# Hardware-Neuron.net
KiCad netlist of a schematic drawn in EAGLE
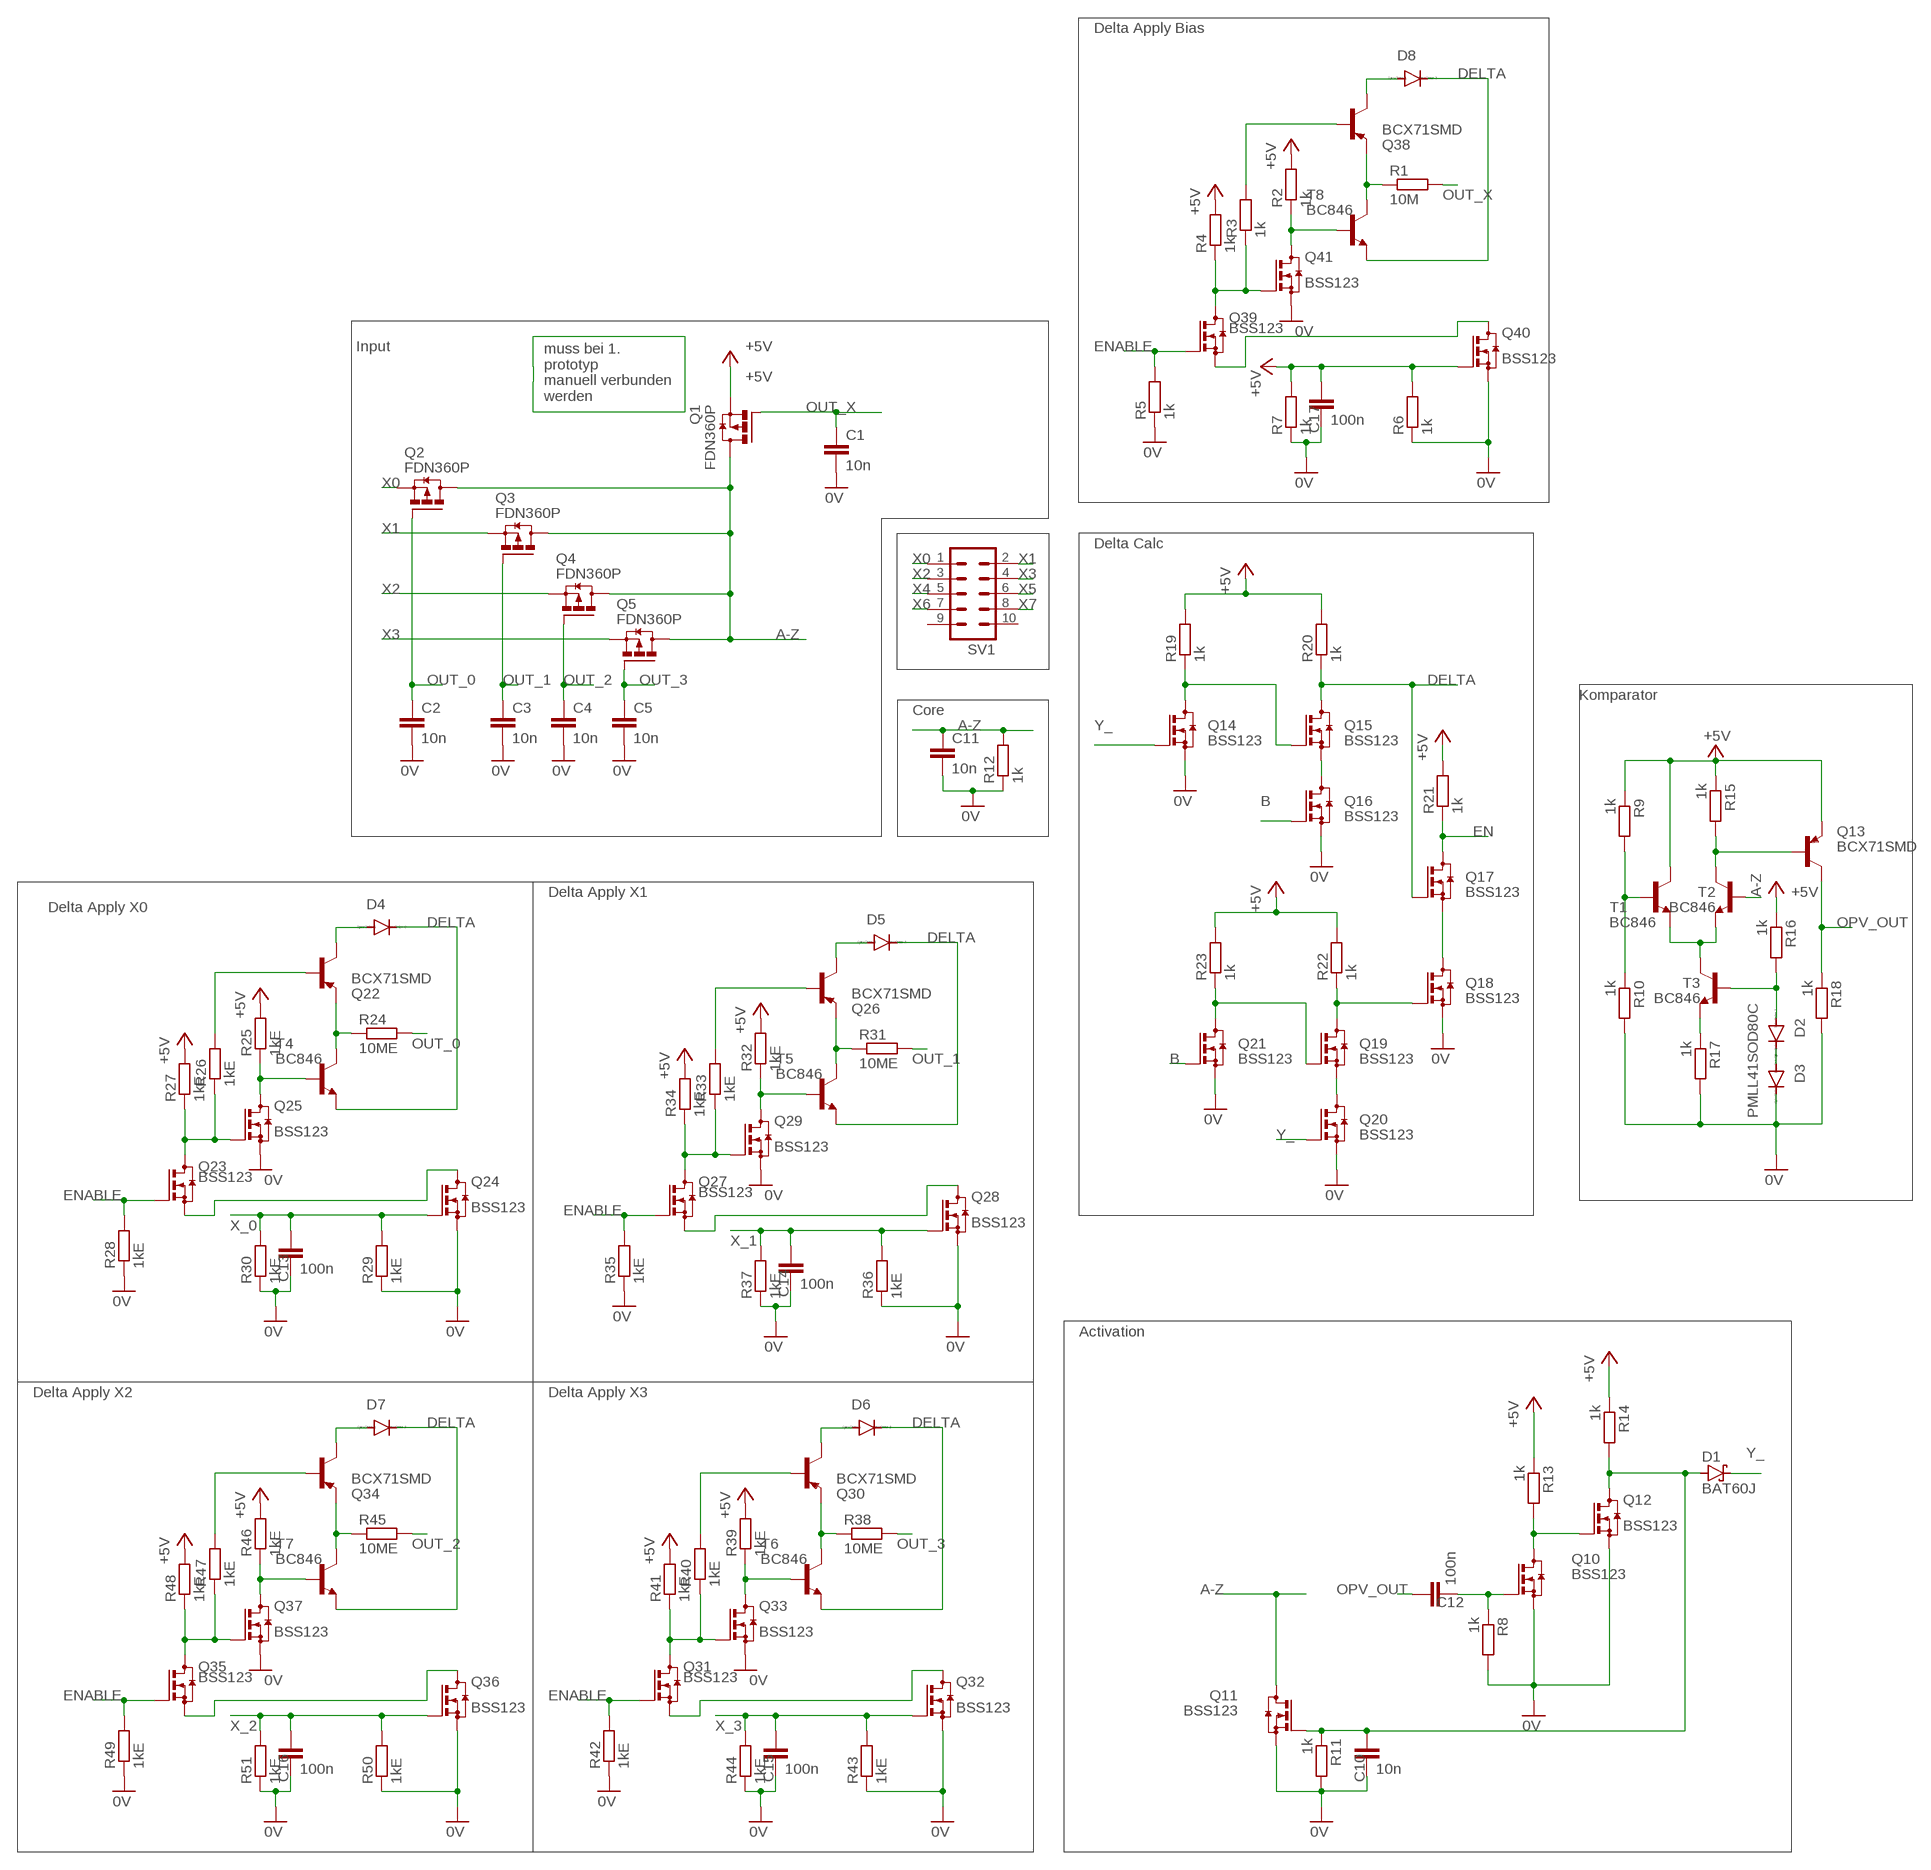
[diagram p0: schematic, sheet 1]

(export (version "E")
  (design (tool "Eeschema 10.0.6"))
  (components
    (comp (ref "C1")
      (value "10n")
      (footprint "eagle-import:C1206")
      (libsource (lib "eagle-import") (part "C-EUC1206"))
    )
    (comp (ref "C2")
      (value "10n")
      (footprint "eagle-import:C1206")
      (libsource (lib "eagle-import") (part "C-EUC1206"))
    )
    (comp (ref "C3")
      (value "10n")
      (footprint "eagle-import:C1206")
      (libsource (lib "eagle-import") (part "C-EUC1206"))
    )
    (comp (ref "C4")
      (value "10n")
      (footprint "eagle-import:C1206")
      (libsource (lib "eagle-import") (part "C-EUC1206"))
    )
    (comp (ref "C5")
      (value "10n")
      (footprint "eagle-import:C1206")
      (libsource (lib "eagle-import") (part "C-EUC1206"))
    )
    (comp (ref "C10")
      (value "10n")
      (footprint "eagle-import:C1206")
      (libsource (lib "eagle-import") (part "C-EUC1206"))
    )
    (comp (ref "C11")
      (value "10n")
      (footprint "eagle-import:C1206")
      (libsource (lib "eagle-import") (part "C-EUC1206"))
    )
    (comp (ref "C12")
      (value "100n")
      (footprint "eagle-import:C1206")
      (libsource (lib "eagle-import") (part "C-EUC1206"))
    )
    (comp (ref "C13")
      (value "100n")
      (footprint "eagle-import:C1206")
      (libsource (lib "eagle-import") (part "C-EUC1206"))
    )
    (comp (ref "C14")
      (value "100n")
      (footprint "eagle-import:C1206")
      (libsource (lib "eagle-import") (part "C-EUC1206"))
    )
    (comp (ref "C15")
      (value "100n")
      (footprint "eagle-import:C1206")
      (libsource (lib "eagle-import") (part "C-EUC1206"))
    )
    (comp (ref "C16")
      (value "100n")
      (footprint "eagle-import:C1206")
      (libsource (lib "eagle-import") (part "C-EUC1206"))
    )
    (comp (ref "C17")
      (value "100n")
      (footprint "eagle-import:C1206")
      (libsource (lib "eagle-import") (part "C-EUC1206"))
    )
    (comp (ref "D1")
      (value "BAT60J")
      (footprint "eagle-import:SOD323_ST")
      (libsource (lib "eagle-import") (part "BAT60J"))
    )
    (comp (ref "D2")
      (value "PMLL41SOD80C")
      (footprint "eagle-import:SOD80C")
      (libsource (lib "eagle-import") (part "PMLL41SOD80C"))
    )
    (comp (ref "D3")
      (value "PMLL41SOD80C")
      (footprint "eagle-import:SOD80C")
      (libsource (lib "eagle-import") (part "PMLL41SOD80C"))
    )
    (comp (ref "D4")
      (value "PMLL41SOD80C")
      (footprint "eagle-import:SOD80C")
      (libsource (lib "eagle-import") (part "PMLL41SOD80C"))
    )
    (comp (ref "D5")
      (value "PMLL41SOD80C")
      (footprint "eagle-import:SOD80C")
      (libsource (lib "eagle-import") (part "PMLL41SOD80C"))
    )
    (comp (ref "D6")
      (value "PMLL41SOD80C")
      (footprint "eagle-import:SOD80C")
      (libsource (lib "eagle-import") (part "PMLL41SOD80C"))
    )
    (comp (ref "D7")
      (value "PMLL41SOD80C")
      (footprint "eagle-import:SOD80C")
      (libsource (lib "eagle-import") (part "PMLL41SOD80C"))
    )
    (comp (ref "D8")
      (value "PMLL41SOD80C")
      (footprint "eagle-import:SOD80C")
      (libsource (lib "eagle-import") (part "PMLL41SOD80C"))
    )
    (comp (ref "Q1")
      (value "FDN360P")
      (footprint "eagle-import:SUPER-SOT3")
      (libsource (lib "eagle-import") (part "FDN360P"))
    )
    (comp (ref "Q2")
      (value "FDN360P")
      (footprint "eagle-import:SUPER-SOT3")
      (libsource (lib "eagle-import") (part "FDN360P"))
    )
    (comp (ref "Q3")
      (value "FDN360P")
      (footprint "eagle-import:SUPER-SOT3")
      (libsource (lib "eagle-import") (part "FDN360P"))
    )
    (comp (ref "Q4")
      (value "FDN360P")
      (footprint "eagle-import:SUPER-SOT3")
      (libsource (lib "eagle-import") (part "FDN360P"))
    )
    (comp (ref "Q5")
      (value "FDN360P")
      (footprint "eagle-import:SUPER-SOT3")
      (libsource (lib "eagle-import") (part "FDN360P"))
    )
    (comp (ref "Q10")
      (value "BSS123")
      (footprint "eagle-import:SOT23")
      (libsource (lib "eagle-import") (part "BSS123"))
    )
    (comp (ref "Q11")
      (value "BSS123")
      (footprint "eagle-import:SOT23")
      (libsource (lib "eagle-import") (part "BSS123"))
    )
    (comp (ref "Q12")
      (value "BSS123")
      (footprint "eagle-import:SOT23")
      (libsource (lib "eagle-import") (part "BSS123"))
    )
    (comp (ref "Q13")
      (value "BCX71SMD")
      (footprint "eagle-import:SOT23")
      (libsource (lib "eagle-import") (part "BCX71SMD"))
    )
    (comp (ref "Q14")
      (value "BSS123")
      (footprint "eagle-import:SOT23")
      (libsource (lib "eagle-import") (part "BSS123"))
    )
    (comp (ref "Q15")
      (value "BSS123")
      (footprint "eagle-import:SOT23")
      (libsource (lib "eagle-import") (part "BSS123"))
    )
    (comp (ref "Q16")
      (value "BSS123")
      (footprint "eagle-import:SOT23")
      (libsource (lib "eagle-import") (part "BSS123"))
    )
    (comp (ref "Q17")
      (value "BSS123")
      (footprint "eagle-import:SOT23")
      (libsource (lib "eagle-import") (part "BSS123"))
    )
    (comp (ref "Q18")
      (value "BSS123")
      (footprint "eagle-import:SOT23")
      (libsource (lib "eagle-import") (part "BSS123"))
    )
    (comp (ref "Q19")
      (value "BSS123")
      (footprint "eagle-import:SOT23")
      (libsource (lib "eagle-import") (part "BSS123"))
    )
    (comp (ref "Q20")
      (value "BSS123")
      (footprint "eagle-import:SOT23")
      (libsource (lib "eagle-import") (part "BSS123"))
    )
    (comp (ref "Q21")
      (value "BSS123")
      (footprint "eagle-import:SOT23")
      (libsource (lib "eagle-import") (part "BSS123"))
    )
    (comp (ref "Q22")
      (value "BCX71SMD")
      (footprint "eagle-import:SOT23")
      (libsource (lib "eagle-import") (part "BCX71SMD"))
    )
    (comp (ref "Q23")
      (value "BSS123")
      (footprint "eagle-import:SOT23")
      (libsource (lib "eagle-import") (part "BSS123"))
    )
    (comp (ref "Q24")
      (value "BSS123")
      (footprint "eagle-import:SOT23")
      (libsource (lib "eagle-import") (part "BSS123"))
    )
    (comp (ref "Q25")
      (value "BSS123")
      (footprint "eagle-import:SOT23")
      (libsource (lib "eagle-import") (part "BSS123"))
    )
    (comp (ref "Q26")
      (value "BCX71SMD")
      (footprint "eagle-import:SOT23")
      (libsource (lib "eagle-import") (part "BCX71SMD"))
    )
    (comp (ref "Q27")
      (value "BSS123")
      (footprint "eagle-import:SOT23")
      (libsource (lib "eagle-import") (part "BSS123"))
    )
    (comp (ref "Q28")
      (value "BSS123")
      (footprint "eagle-import:SOT23")
      (libsource (lib "eagle-import") (part "BSS123"))
    )
    (comp (ref "Q29")
      (value "BSS123")
      (footprint "eagle-import:SOT23")
      (libsource (lib "eagle-import") (part "BSS123"))
    )
    (comp (ref "Q30")
      (value "BCX71SMD")
      (footprint "eagle-import:SOT23")
      (libsource (lib "eagle-import") (part "BCX71SMD"))
    )
    (comp (ref "Q31")
      (value "BSS123")
      (footprint "eagle-import:SOT23")
      (libsource (lib "eagle-import") (part "BSS123"))
    )
    (comp (ref "Q32")
      (value "BSS123")
      (footprint "eagle-import:SOT23")
      (libsource (lib "eagle-import") (part "BSS123"))
    )
    (comp (ref "Q33")
      (value "BSS123")
      (footprint "eagle-import:SOT23")
      (libsource (lib "eagle-import") (part "BSS123"))
    )
    (comp (ref "Q34")
      (value "BCX71SMD")
      (footprint "eagle-import:SOT23")
      (libsource (lib "eagle-import") (part "BCX71SMD"))
    )
    (comp (ref "Q35")
      (value "BSS123")
      (footprint "eagle-import:SOT23")
      (libsource (lib "eagle-import") (part "BSS123"))
    )
    (comp (ref "Q36")
      (value "BSS123")
      (footprint "eagle-import:SOT23")
      (libsource (lib "eagle-import") (part "BSS123"))
    )
    (comp (ref "Q37")
      (value "BSS123")
      (footprint "eagle-import:SOT23")
      (libsource (lib "eagle-import") (part "BSS123"))
    )
    (comp (ref "Q38")
      (value "BCX71SMD")
      (footprint "eagle-import:SOT23")
      (libsource (lib "eagle-import") (part "BCX71SMD"))
    )
    (comp (ref "Q39")
      (value "BSS123")
      (footprint "eagle-import:SOT23")
      (libsource (lib "eagle-import") (part "BSS123"))
    )
    (comp (ref "Q40")
      (value "BSS123")
      (footprint "eagle-import:SOT23")
      (libsource (lib "eagle-import") (part "BSS123"))
    )
    (comp (ref "Q41")
      (value "BSS123")
      (footprint "eagle-import:SOT23")
      (libsource (lib "eagle-import") (part "BSS123"))
    )
    (comp (ref "R1")
      (value "10M")
      (footprint "eagle-import:R1206")
      (libsource (lib "eagle-import") (part "R-EU_R1206"))
    )
    (comp (ref "R2")
      (value "1k")
      (footprint "eagle-import:R1206")
      (libsource (lib "eagle-import") (part "R-EU_R1206"))
    )
    (comp (ref "R3")
      (value "1k")
      (footprint "eagle-import:R1206")
      (libsource (lib "eagle-import") (part "R-EU_R1206"))
    )
    (comp (ref "R4")
      (value "1k")
      (footprint "eagle-import:R1206")
      (libsource (lib "eagle-import") (part "R-EU_R1206"))
    )
    (comp (ref "R5")
      (value "1k")
      (footprint "eagle-import:R1206")
      (libsource (lib "eagle-import") (part "R-EU_R1206"))
    )
    (comp (ref "R6")
      (value "1k")
      (footprint "eagle-import:R1206")
      (libsource (lib "eagle-import") (part "R-EU_R1206"))
    )
    (comp (ref "R7")
      (value "1k")
      (footprint "eagle-import:R1206")
      (libsource (lib "eagle-import") (part "R-EU_R1206"))
    )
    (comp (ref "R8")
      (value "1k")
      (footprint "eagle-import:R1206")
      (libsource (lib "eagle-import") (part "R-EU_R1206"))
    )
    (comp (ref "R9")
      (value "1k")
      (footprint "eagle-import:R1206")
      (libsource (lib "eagle-import") (part "R-EU_R1206"))
    )
    (comp (ref "R10")
      (value "1k")
      (footprint "eagle-import:R1206")
      (libsource (lib "eagle-import") (part "R-EU_R1206"))
    )
    (comp (ref "R11")
      (value "1k")
      (footprint "eagle-import:R1206")
      (libsource (lib "eagle-import") (part "R-EU_R1206"))
    )
    (comp (ref "R12")
      (value "1k")
      (footprint "eagle-import:R1206")
      (libsource (lib "eagle-import") (part "R-EU_R1206"))
    )
    (comp (ref "R13")
      (value "1k")
      (footprint "eagle-import:R1206")
      (libsource (lib "eagle-import") (part "R-EU_R1206"))
    )
    (comp (ref "R14")
      (value "1k")
      (footprint "eagle-import:R1206")
      (libsource (lib "eagle-import") (part "R-EU_R1206"))
    )
    (comp (ref "R15")
      (value "1k")
      (footprint "eagle-import:R1206")
      (libsource (lib "eagle-import") (part "R-EU_R1206"))
    )
    (comp (ref "R16")
      (value "1k")
      (footprint "eagle-import:R1206")
      (libsource (lib "eagle-import") (part "R-EU_R1206"))
    )
    (comp (ref "R17")
      (value "1k")
      (footprint "eagle-import:R1206")
      (libsource (lib "eagle-import") (part "R-EU_R1206"))
    )
    (comp (ref "R18")
      (value "1k")
      (footprint "eagle-import:R1206")
      (libsource (lib "eagle-import") (part "R-EU_R1206"))
    )
    (comp (ref "R19")
      (value "1k")
      (footprint "eagle-import:R1206")
      (libsource (lib "eagle-import") (part "R-EU_R1206"))
    )
    (comp (ref "R20")
      (value "1k")
      (footprint "eagle-import:R1206")
      (libsource (lib "eagle-import") (part "R-EU_R1206"))
    )
    (comp (ref "R21")
      (value "1k")
      (footprint "eagle-import:R1206")
      (libsource (lib "eagle-import") (part "R-EU_R1206"))
    )
    (comp (ref "R22")
      (value "1k")
      (footprint "eagle-import:R1206")
      (libsource (lib "eagle-import") (part "R-EU_R1206"))
    )
    (comp (ref "R23")
      (value "1k")
      (footprint "eagle-import:R1206")
      (libsource (lib "eagle-import") (part "R-EU_R1206"))
    )
    (comp (ref "R24")
      (value "10ME")
      (footprint "eagle-import:R1206")
      (libsource (lib "eagle-import") (part "R-EU_R1206"))
    )
    (comp (ref "R25")
      (value "1kE")
      (footprint "eagle-import:R1206")
      (libsource (lib "eagle-import") (part "R-EU_R1206"))
    )
    (comp (ref "R26")
      (value "1kE")
      (footprint "eagle-import:R1206")
      (libsource (lib "eagle-import") (part "R-EU_R1206"))
    )
    (comp (ref "R27")
      (value "1kE")
      (footprint "eagle-import:R1206")
      (libsource (lib "eagle-import") (part "R-EU_R1206"))
    )
    (comp (ref "R28")
      (value "1kE")
      (footprint "eagle-import:R1206")
      (libsource (lib "eagle-import") (part "R-EU_R1206"))
    )
    (comp (ref "R29")
      (value "1kE")
      (footprint "eagle-import:R1206")
      (libsource (lib "eagle-import") (part "R-EU_R1206"))
    )
    (comp (ref "R30")
      (value "1kE")
      (footprint "eagle-import:R1206")
      (libsource (lib "eagle-import") (part "R-EU_R1206"))
    )
    (comp (ref "R31")
      (value "10ME")
      (footprint "eagle-import:R1206")
      (libsource (lib "eagle-import") (part "R-EU_R1206"))
    )
    (comp (ref "R32")
      (value "1kE")
      (footprint "eagle-import:R1206")
      (libsource (lib "eagle-import") (part "R-EU_R1206"))
    )
    (comp (ref "R33")
      (value "1kE")
      (footprint "eagle-import:R1206")
      (libsource (lib "eagle-import") (part "R-EU_R1206"))
    )
    (comp (ref "R34")
      (value "1kE")
      (footprint "eagle-import:R1206")
      (libsource (lib "eagle-import") (part "R-EU_R1206"))
    )
    (comp (ref "R35")
      (value "1kE")
      (footprint "eagle-import:R1206")
      (libsource (lib "eagle-import") (part "R-EU_R1206"))
    )
    (comp (ref "R36")
      (value "1kE")
      (footprint "eagle-import:R1206")
      (libsource (lib "eagle-import") (part "R-EU_R1206"))
    )
    (comp (ref "R37")
      (value "1kE")
      (footprint "eagle-import:R1206")
      (libsource (lib "eagle-import") (part "R-EU_R1206"))
    )
    (comp (ref "R38")
      (value "10ME")
      (footprint "eagle-import:R1206")
      (libsource (lib "eagle-import") (part "R-EU_R1206"))
    )
    (comp (ref "R39")
      (value "1kE")
      (footprint "eagle-import:R1206")
      (libsource (lib "eagle-import") (part "R-EU_R1206"))
    )
    (comp (ref "R40")
      (value "1kE")
      (footprint "eagle-import:R1206")
      (libsource (lib "eagle-import") (part "R-EU_R1206"))
    )
    (comp (ref "R41")
      (value "1kE")
      (footprint "eagle-import:R1206")
      (libsource (lib "eagle-import") (part "R-EU_R1206"))
    )
    (comp (ref "R42")
      (value "1kE")
      (footprint "eagle-import:R1206")
      (libsource (lib "eagle-import") (part "R-EU_R1206"))
    )
    (comp (ref "R43")
      (value "1kE")
      (footprint "eagle-import:R1206")
      (libsource (lib "eagle-import") (part "R-EU_R1206"))
    )
    (comp (ref "R44")
      (value "1kE")
      (footprint "eagle-import:R1206")
      (libsource (lib "eagle-import") (part "R-EU_R1206"))
    )
    (comp (ref "R45")
      (value "10ME")
      (footprint "eagle-import:R1206")
      (libsource (lib "eagle-import") (part "R-EU_R1206"))
    )
    (comp (ref "R46")
      (value "1kE")
      (footprint "eagle-import:R1206")
      (libsource (lib "eagle-import") (part "R-EU_R1206"))
    )
    (comp (ref "R47")
      (value "1kE")
      (footprint "eagle-import:R1206")
      (libsource (lib "eagle-import") (part "R-EU_R1206"))
    )
    (comp (ref "R48")
      (value "1kE")
      (footprint "eagle-import:R1206")
      (libsource (lib "eagle-import") (part "R-EU_R1206"))
    )
    (comp (ref "R49")
      (value "1kE")
      (footprint "eagle-import:R1206")
      (libsource (lib "eagle-import") (part "R-EU_R1206"))
    )
    (comp (ref "R50")
      (value "1kE")
      (footprint "eagle-import:R1206")
      (libsource (lib "eagle-import") (part "R-EU_R1206"))
    )
    (comp (ref "R51")
      (value "1kE")
      (footprint "eagle-import:R1206")
      (libsource (lib "eagle-import") (part "R-EU_R1206"))
    )
    (comp (ref "SV1")
      (value "ML10")
      (footprint "eagle-import:ML10")
      (libsource (lib "eagle-import") (part "ML10"))
    )
    (comp (ref "T1")
      (value "BC846")
      (footprint "eagle-import:SOT23")
      (libsource (lib "eagle-import") (part "BC846"))
    )
    (comp (ref "T2")
      (value "BC846")
      (footprint "eagle-import:SOT23")
      (libsource (lib "eagle-import") (part "BC846"))
    )
    (comp (ref "T3")
      (value "BC846")
      (footprint "eagle-import:SOT23")
      (libsource (lib "eagle-import") (part "BC846"))
    )
    (comp (ref "T4")
      (value "BC846")
      (footprint "eagle-import:SOT23")
      (libsource (lib "eagle-import") (part "BC846"))
    )
    (comp (ref "T5")
      (value "BC846")
      (footprint "eagle-import:SOT23")
      (libsource (lib "eagle-import") (part "BC846"))
    )
    (comp (ref "T6")
      (value "BC846")
      (footprint "eagle-import:SOT23")
      (libsource (lib "eagle-import") (part "BC846"))
    )
    (comp (ref "T7")
      (value "BC846")
      (footprint "eagle-import:SOT23")
      (libsource (lib "eagle-import") (part "BC846"))
    )
    (comp (ref "T8")
      (value "BC846")
      (footprint "eagle-import:SOT23")
      (libsource (lib "eagle-import") (part "BC846"))
    )
  )
  (nets
    (net (code "1") (name "+5V") (class "Default")
      (node (ref "C17") (pin "1") (pinfunction "1_1") (pintype "passive"))
      (node (ref "Q1") (pin "2") (pinfunction "S_2") (pintype "passive"))
      (node (ref "Q13") (pin "2") (pinfunction "E_2") (pintype "passive"))
      (node (ref "Q40") (pin "1") (pinfunction "G_1") (pintype "passive"))
      (node (ref "R13") (pin "1") (pinfunction "1_1") (pintype "passive"))
      (node (ref "R14") (pin "1") (pinfunction "1_1") (pintype "passive"))
      (node (ref "R15") (pin "1") (pinfunction "1_1") (pintype "passive"))
      (node (ref "R16") (pin "1") (pinfunction "1_1") (pintype "passive"))
      (node (ref "R19") (pin "2") (pinfunction "2_2") (pintype "passive"))
      (node (ref "R2") (pin "2") (pinfunction "2_2") (pintype "passive"))
      (node (ref "R20") (pin "2") (pinfunction "2_2") (pintype "passive"))
      (node (ref "R21") (pin "2") (pinfunction "2_2") (pintype "passive"))
      (node (ref "R22") (pin "2") (pinfunction "2_2") (pintype "passive"))
      (node (ref "R23") (pin "2") (pinfunction "2_2") (pintype "passive"))
      (node (ref "R25") (pin "2") (pinfunction "2_2") (pintype "passive"))
      (node (ref "R27") (pin "2") (pinfunction "2_2") (pintype "passive"))
      (node (ref "R32") (pin "2") (pinfunction "2_2") (pintype "passive"))
      (node (ref "R34") (pin "2") (pinfunction "2_2") (pintype "passive"))
      (node (ref "R39") (pin "2") (pinfunction "2_2") (pintype "passive"))
      (node (ref "R4") (pin "2") (pinfunction "2_2") (pintype "passive"))
      (node (ref "R41") (pin "2") (pinfunction "2_2") (pintype "passive"))
      (node (ref "R46") (pin "2") (pinfunction "2_2") (pintype "passive"))
      (node (ref "R48") (pin "2") (pinfunction "2_2") (pintype "passive"))
      (node (ref "R6") (pin "2") (pinfunction "2_2") (pintype "passive"))
      (node (ref "R7") (pin "2") (pinfunction "2_2") (pintype "passive"))
      (node (ref "R9") (pin "1") (pinfunction "1_1") (pintype "passive"))
      (node (ref "T1") (pin "3") (pinfunction "C_3") (pintype "passive"))
    )
    (net (code "2") (name "/A-Z") (class "Default")
      (node (ref "C11") (pin "1") (pinfunction "1_1") (pintype "passive"))
      (node (ref "Q1") (pin "3") (pinfunction "D_3") (pintype "passive"))
      (node (ref "Q11") (pin "3") (pinfunction "D_3") (pintype "passive"))
      (node (ref "Q2") (pin "3") (pinfunction "D_3") (pintype "passive"))
      (node (ref "Q3") (pin "3") (pinfunction "D_3") (pintype "passive"))
      (node (ref "Q4") (pin "3") (pinfunction "D_3") (pintype "passive"))
      (node (ref "Q5") (pin "3") (pinfunction "D_3") (pintype "passive"))
      (node (ref "R12") (pin "2") (pinfunction "2_2") (pintype "passive"))
      (node (ref "T2") (pin "1") (pinfunction "B_1") (pintype "passive"))
    )
    (net (code "3") (name "/B") (class "Default")
      (node (ref "Q16") (pin "1") (pinfunction "G_1") (pintype "passive"))
      (node (ref "Q21") (pin "1") (pinfunction "G_1") (pintype "passive"))
    )
    (net (code "4") (name "/DELTA") (class "Default")
      (node (ref "D4") (pin "C") (pinfunction "C_C") (pintype "passive"))
      (node (ref "D5") (pin "C") (pinfunction "C_C") (pintype "passive"))
      (node (ref "D6") (pin "C") (pinfunction "C_C") (pintype "passive"))
      (node (ref "D7") (pin "C") (pinfunction "C_C") (pintype "passive"))
      (node (ref "D8") (pin "C") (pinfunction "C_C") (pintype "passive"))
      (node (ref "Q15") (pin "3") (pinfunction "D_3") (pintype "passive"))
      (node (ref "Q17") (pin "1") (pinfunction "G_1") (pintype "passive"))
      (node (ref "R20") (pin "1") (pinfunction "1_1") (pintype "passive"))
      (node (ref "T4") (pin "2") (pinfunction "E_2") (pintype "passive"))
      (node (ref "T5") (pin "2") (pinfunction "E_2") (pintype "passive"))
      (node (ref "T6") (pin "2") (pinfunction "E_2") (pintype "passive"))
      (node (ref "T7") (pin "2") (pinfunction "E_2") (pintype "passive"))
      (node (ref "T8") (pin "2") (pinfunction "E_2") (pintype "passive"))
    )
    (net (code "5") (name "/EN") (class "Default")
      (node (ref "Q17") (pin "3") (pinfunction "D_3") (pintype "passive"))
      (node (ref "R21") (pin "1") (pinfunction "1_1") (pintype "passive"))
    )
    (net (code "6") (name "/ENABLE") (class "Default")
      (node (ref "Q23") (pin "1") (pinfunction "G_1") (pintype "passive"))
      (node (ref "Q27") (pin "1") (pinfunction "G_1") (pintype "passive"))
      (node (ref "Q31") (pin "1") (pinfunction "G_1") (pintype "passive"))
      (node (ref "Q35") (pin "1") (pinfunction "G_1") (pintype "passive"))
      (node (ref "Q39") (pin "1") (pinfunction "G_1") (pintype "passive"))
      (node (ref "R28") (pin "2") (pinfunction "2_2") (pintype "passive"))
      (node (ref "R35") (pin "2") (pinfunction "2_2") (pintype "passive"))
      (node (ref "R42") (pin "2") (pinfunction "2_2") (pintype "passive"))
      (node (ref "R49") (pin "2") (pinfunction "2_2") (pintype "passive"))
      (node (ref "R5") (pin "2") (pinfunction "2_2") (pintype "passive"))
    )
    (net (code "7") (name "/OPV_OUT") (class "Default")
      (node (ref "C12") (pin "1") (pinfunction "1_1") (pintype "passive"))
      (node (ref "Q13") (pin "3") (pinfunction "C_3") (pintype "passive"))
      (node (ref "R18") (pin "1") (pinfunction "1_1") (pintype "passive"))
    )
    (net (code "8") (name "/OUT_0") (class "Default")
      (node (ref "C2") (pin "1") (pinfunction "1_1") (pintype "passive"))
      (node (ref "Q2") (pin "1") (pinfunction "G_1") (pintype "passive"))
      (node (ref "R24") (pin "2") (pinfunction "2_2") (pintype "passive"))
    )
    (net (code "9") (name "/OUT_1") (class "Default")
      (node (ref "C3") (pin "1") (pinfunction "1_1") (pintype "passive"))
      (node (ref "Q3") (pin "1") (pinfunction "G_1") (pintype "passive"))
      (node (ref "R31") (pin "2") (pinfunction "2_2") (pintype "passive"))
    )
    (net (code "10") (name "/OUT_2") (class "Default")
      (node (ref "C4") (pin "1") (pinfunction "1_1") (pintype "passive"))
      (node (ref "Q4") (pin "1") (pinfunction "G_1") (pintype "passive"))
      (node (ref "R45") (pin "2") (pinfunction "2_2") (pintype "passive"))
    )
    (net (code "11") (name "/OUT_3") (class "Default")
      (node (ref "C5") (pin "1") (pinfunction "1_1") (pintype "passive"))
      (node (ref "Q5") (pin "1") (pinfunction "G_1") (pintype "passive"))
      (node (ref "R38") (pin "2") (pinfunction "2_2") (pintype "passive"))
    )
    (net (code "12") (name "/OUT_X") (class "Default")
      (node (ref "C1") (pin "1") (pinfunction "1_1") (pintype "passive"))
      (node (ref "Q1") (pin "1") (pinfunction "G_1") (pintype "passive"))
      (node (ref "R1") (pin "2") (pinfunction "2_2") (pintype "passive"))
    )
    (net (code "13") (name "/X0") (class "Default")
      (node (ref "Q2") (pin "2") (pinfunction "S_2") (pintype "passive"))
      (node (ref "SV1") (pin "1") (pinfunction "1_1") (pintype "passive"))
    )
    (net (code "14") (name "/X1") (class "Default")
      (node (ref "Q3") (pin "2") (pinfunction "S_2") (pintype "passive"))
      (node (ref "SV1") (pin "2") (pinfunction "2_2") (pintype "passive"))
    )
    (net (code "15") (name "/X2") (class "Default")
      (node (ref "Q4") (pin "2") (pinfunction "S_2") (pintype "passive"))
      (node (ref "SV1") (pin "3") (pinfunction "3_3") (pintype "passive"))
    )
    (net (code "16") (name "/X3") (class "Default")
      (node (ref "Q5") (pin "2") (pinfunction "S_2") (pintype "passive"))
      (node (ref "SV1") (pin "4") (pinfunction "4_4") (pintype "passive"))
    )
    (net (code "17") (name "/X4") (class "Default")
      (node (ref "SV1") (pin "5") (pinfunction "5_5") (pintype "passive"))
    )
    (net (code "18") (name "/X5") (class "Default")
      (node (ref "SV1") (pin "6") (pinfunction "6_6") (pintype "passive"))
    )
    (net (code "19") (name "/X6") (class "Default")
      (node (ref "SV1") (pin "7") (pinfunction "7_7") (pintype "passive"))
    )
    (net (code "20") (name "/X7") (class "Default")
      (node (ref "SV1") (pin "8") (pinfunction "8_8") (pintype "passive"))
    )
    (net (code "21") (name "/X_0") (class "Default")
      (node (ref "C13") (pin "1") (pinfunction "1_1") (pintype "passive"))
      (node (ref "Q24") (pin "1") (pinfunction "G_1") (pintype "passive"))
      (node (ref "R29") (pin "2") (pinfunction "2_2") (pintype "passive"))
      (node (ref "R30") (pin "2") (pinfunction "2_2") (pintype "passive"))
    )
    (net (code "22") (name "/X_1") (class "Default")
      (node (ref "C14") (pin "1") (pinfunction "1_1") (pintype "passive"))
      (node (ref "Q28") (pin "1") (pinfunction "G_1") (pintype "passive"))
      (node (ref "R36") (pin "2") (pinfunction "2_2") (pintype "passive"))
      (node (ref "R37") (pin "2") (pinfunction "2_2") (pintype "passive"))
    )
    (net (code "23") (name "/X_2") (class "Default")
      (node (ref "C16") (pin "1") (pinfunction "1_1") (pintype "passive"))
      (node (ref "Q36") (pin "1") (pinfunction "G_1") (pintype "passive"))
      (node (ref "R50") (pin "2") (pinfunction "2_2") (pintype "passive"))
      (node (ref "R51") (pin "2") (pinfunction "2_2") (pintype "passive"))
    )
    (net (code "24") (name "/X_3") (class "Default")
      (node (ref "C15") (pin "1") (pinfunction "1_1") (pintype "passive"))
      (node (ref "Q32") (pin "1") (pinfunction "G_1") (pintype "passive"))
      (node (ref "R43") (pin "2") (pinfunction "2_2") (pintype "passive"))
      (node (ref "R44") (pin "2") (pinfunction "2_2") (pintype "passive"))
    )
    (net (code "25") (name "/Y_") (class "Default")
      (node (ref "D1") (pin "C") (pinfunction "C_C") (pintype "passive"))
      (node (ref "Q14") (pin "1") (pinfunction "G_1") (pintype "passive"))
      (node (ref "Q20") (pin "1") (pinfunction "G_1") (pintype "passive"))
    )
    (net (code "26") (name "0V") (class "Default")
      (node (ref "C1") (pin "2") (pinfunction "2_2") (pintype "passive"))
      (node (ref "C10") (pin "2") (pinfunction "2_2") (pintype "passive"))
      (node (ref "C11") (pin "2") (pinfunction "2_2") (pintype "passive"))
      (node (ref "C13") (pin "2") (pinfunction "2_2") (pintype "passive"))
      (node (ref "C14") (pin "2") (pinfunction "2_2") (pintype "passive"))
      (node (ref "C15") (pin "2") (pinfunction "2_2") (pintype "passive"))
      (node (ref "C16") (pin "2") (pinfunction "2_2") (pintype "passive"))
      (node (ref "C17") (pin "2") (pinfunction "2_2") (pintype "passive"))
      (node (ref "C2") (pin "2") (pinfunction "2_2") (pintype "passive"))
      (node (ref "C3") (pin "2") (pinfunction "2_2") (pintype "passive"))
      (node (ref "C4") (pin "2") (pinfunction "2_2") (pintype "passive"))
      (node (ref "C5") (pin "2") (pinfunction "2_2") (pintype "passive"))
      (node (ref "D3") (pin "C") (pinfunction "C_C") (pintype "passive"))
      (node (ref "Q10") (pin "2") (pinfunction "S_2") (pintype "passive"))
      (node (ref "Q11") (pin "2") (pinfunction "S_2") (pintype "passive"))
      (node (ref "Q12") (pin "2") (pinfunction "S_2") (pintype "passive"))
      (node (ref "Q14") (pin "2") (pinfunction "S_2") (pintype "passive"))
      (node (ref "Q16") (pin "2") (pinfunction "S_2") (pintype "passive"))
      (node (ref "Q18") (pin "2") (pinfunction "S_2") (pintype "passive"))
      (node (ref "Q20") (pin "2") (pinfunction "S_2") (pintype "passive"))
      (node (ref "Q21") (pin "2") (pinfunction "S_2") (pintype "passive"))
      (node (ref "Q24") (pin "2") (pinfunction "S_2") (pintype "passive"))
      (node (ref "Q25") (pin "2") (pinfunction "S_2") (pintype "passive"))
      (node (ref "Q28") (pin "2") (pinfunction "S_2") (pintype "passive"))
      (node (ref "Q29") (pin "2") (pinfunction "S_2") (pintype "passive"))
      (node (ref "Q32") (pin "2") (pinfunction "S_2") (pintype "passive"))
      (node (ref "Q33") (pin "2") (pinfunction "S_2") (pintype "passive"))
      (node (ref "Q36") (pin "2") (pinfunction "S_2") (pintype "passive"))
      (node (ref "Q37") (pin "2") (pinfunction "S_2") (pintype "passive"))
      (node (ref "Q40") (pin "2") (pinfunction "S_2") (pintype "passive"))
      (node (ref "Q41") (pin "2") (pinfunction "S_2") (pintype "passive"))
      (node (ref "R10") (pin "2") (pinfunction "2_2") (pintype "passive"))
      (node (ref "R11") (pin "2") (pinfunction "2_2") (pintype "passive"))
      (node (ref "R12") (pin "1") (pinfunction "1_1") (pintype "passive"))
      (node (ref "R17") (pin "2") (pinfunction "2_2") (pintype "passive"))
      (node (ref "R18") (pin "2") (pinfunction "2_2") (pintype "passive"))
      (node (ref "R28") (pin "1") (pinfunction "1_1") (pintype "passive"))
      (node (ref "R29") (pin "1") (pinfunction "1_1") (pintype "passive"))
      (node (ref "R30") (pin "1") (pinfunction "1_1") (pintype "passive"))
      (node (ref "R35") (pin "1") (pinfunction "1_1") (pintype "passive"))
      (node (ref "R36") (pin "1") (pinfunction "1_1") (pintype "passive"))
      (node (ref "R37") (pin "1") (pinfunction "1_1") (pintype "passive"))
      (node (ref "R42") (pin "1") (pinfunction "1_1") (pintype "passive"))
      (node (ref "R43") (pin "1") (pinfunction "1_1") (pintype "passive"))
      (node (ref "R44") (pin "1") (pinfunction "1_1") (pintype "passive"))
      (node (ref "R49") (pin "1") (pinfunction "1_1") (pintype "passive"))
      (node (ref "R5") (pin "1") (pinfunction "1_1") (pintype "passive"))
      (node (ref "R50") (pin "1") (pinfunction "1_1") (pintype "passive"))
      (node (ref "R51") (pin "1") (pinfunction "1_1") (pintype "passive"))
      (node (ref "R6") (pin "1") (pinfunction "1_1") (pintype "passive"))
      (node (ref "R7") (pin "1") (pinfunction "1_1") (pintype "passive"))
      (node (ref "R8") (pin "2") (pinfunction "2_2") (pintype "passive"))
    )
    (net (code "27") (name "Net-(D2-PadC)") (class "Default")
      (node (ref "D2") (pin "C") (pinfunction "C_C") (pintype "passive"))
      (node (ref "D3") (pin "A") (pinfunction "A_A") (pintype "passive"))
    )
    (net (code "28") (name "Net-(Q10-D)") (class "Default")
      (node (ref "Q10") (pin "3") (pinfunction "D_3") (pintype "passive"))
      (node (ref "Q12") (pin "1") (pinfunction "G_1") (pintype "passive"))
      (node (ref "R13") (pin "2") (pinfunction "2_2") (pintype "passive"))
    )
    (net (code "29") (name "Net-(Q10-G)") (class "Default")
      (node (ref "C12") (pin "2") (pinfunction "2_2") (pintype "passive"))
      (node (ref "Q10") (pin "1") (pinfunction "G_1") (pintype "passive"))
      (node (ref "R8") (pin "1") (pinfunction "1_1") (pintype "passive"))
    )
    (net (code "30") (name "Net-(Q11-G)") (class "Default")
      (node (ref "C10") (pin "1") (pinfunction "1_1") (pintype "passive"))
      (node (ref "D1") (pin "A") (pinfunction "A_A") (pintype "passive"))
      (node (ref "Q11") (pin "1") (pinfunction "G_1") (pintype "passive"))
      (node (ref "Q12") (pin "3") (pinfunction "D_3") (pintype "passive"))
      (node (ref "R11") (pin "1") (pinfunction "1_1") (pintype "passive"))
      (node (ref "R14") (pin "2") (pinfunction "2_2") (pintype "passive"))
    )
    (net (code "31") (name "Net-(Q13-B)") (class "Default")
      (node (ref "Q13") (pin "1") (pinfunction "B_1") (pintype "passive"))
      (node (ref "R15") (pin "2") (pinfunction "2_2") (pintype "passive"))
      (node (ref "T2") (pin "3") (pinfunction "C_3") (pintype "passive"))
    )
    (net (code "32") (name "Net-(Q14-D)") (class "Default")
      (node (ref "Q14") (pin "3") (pinfunction "D_3") (pintype "passive"))
      (node (ref "Q15") (pin "1") (pinfunction "G_1") (pintype "passive"))
      (node (ref "R19") (pin "1") (pinfunction "1_1") (pintype "passive"))
    )
    (net (code "33") (name "Net-(Q15-S)") (class "Default")
      (node (ref "Q15") (pin "2") (pinfunction "S_2") (pintype "passive"))
      (node (ref "Q16") (pin "3") (pinfunction "D_3") (pintype "passive"))
    )
    (net (code "34") (name "Net-(Q17-S)") (class "Default")
      (node (ref "Q17") (pin "2") (pinfunction "S_2") (pintype "passive"))
      (node (ref "Q18") (pin "3") (pinfunction "D_3") (pintype "passive"))
    )
    (net (code "35") (name "Net-(Q18-G)") (class "Default")
      (node (ref "Q18") (pin "1") (pinfunction "G_1") (pintype "passive"))
      (node (ref "Q19") (pin "3") (pinfunction "D_3") (pintype "passive"))
      (node (ref "R22") (pin "1") (pinfunction "1_1") (pintype "passive"))
    )
    (net (code "36") (name "Net-(Q19-G)") (class "Default")
      (node (ref "Q19") (pin "1") (pinfunction "G_1") (pintype "passive"))
      (node (ref "Q21") (pin "3") (pinfunction "D_3") (pintype "passive"))
      (node (ref "R23") (pin "1") (pinfunction "1_1") (pintype "passive"))
    )
    (net (code "37") (name "Net-(Q19-S)") (class "Default")
      (node (ref "Q19") (pin "2") (pinfunction "S_2") (pintype "passive"))
      (node (ref "Q20") (pin "3") (pinfunction "D_3") (pintype "passive"))
    )
    (net (code "38") (name "Net-(Q22-B)") (class "Default")
      (node (ref "Q22") (pin "1") (pinfunction "B_1") (pintype "passive"))
      (node (ref "R26") (pin "2") (pinfunction "2_2") (pintype "passive"))
    )
    (net (code "39") (name "Net-(Q22-C)") (class "Default")
      (node (ref "D4") (pin "A") (pinfunction "A_A") (pintype "passive"))
      (node (ref "Q22") (pin "3") (pinfunction "C_3") (pintype "passive"))
    )
    (net (code "40") (name "Net-(Q22-E)") (class "Default")
      (node (ref "Q22") (pin "2") (pinfunction "E_2") (pintype "passive"))
      (node (ref "R24") (pin "1") (pinfunction "1_1") (pintype "passive"))
      (node (ref "T4") (pin "3") (pinfunction "C_3") (pintype "passive"))
    )
    (net (code "41") (name "Net-(Q23-D)") (class "Default")
      (node (ref "Q23") (pin "3") (pinfunction "D_3") (pintype "passive"))
      (node (ref "Q25") (pin "1") (pinfunction "G_1") (pintype "passive"))
      (node (ref "R26") (pin "1") (pinfunction "1_1") (pintype "passive"))
      (node (ref "R27") (pin "1") (pinfunction "1_1") (pintype "passive"))
    )
    (net (code "42") (name "Net-(Q23-S)") (class "Default")
      (node (ref "Q23") (pin "2") (pinfunction "S_2") (pintype "passive"))
      (node (ref "Q24") (pin "3") (pinfunction "D_3") (pintype "passive"))
    )
    (net (code "43") (name "Net-(Q25-D)") (class "Default")
      (node (ref "Q25") (pin "3") (pinfunction "D_3") (pintype "passive"))
      (node (ref "R25") (pin "1") (pinfunction "1_1") (pintype "passive"))
      (node (ref "T4") (pin "1") (pinfunction "B_1") (pintype "passive"))
    )
    (net (code "44") (name "Net-(Q26-B)") (class "Default")
      (node (ref "Q26") (pin "1") (pinfunction "B_1") (pintype "passive"))
      (node (ref "R33") (pin "2") (pinfunction "2_2") (pintype "passive"))
    )
    (net (code "45") (name "Net-(Q26-C)") (class "Default")
      (node (ref "D5") (pin "A") (pinfunction "A_A") (pintype "passive"))
      (node (ref "Q26") (pin "3") (pinfunction "C_3") (pintype "passive"))
    )
    (net (code "46") (name "Net-(Q26-E)") (class "Default")
      (node (ref "Q26") (pin "2") (pinfunction "E_2") (pintype "passive"))
      (node (ref "R31") (pin "1") (pinfunction "1_1") (pintype "passive"))
      (node (ref "T5") (pin "3") (pinfunction "C_3") (pintype "passive"))
    )
    (net (code "47") (name "Net-(Q27-D)") (class "Default")
      (node (ref "Q27") (pin "3") (pinfunction "D_3") (pintype "passive"))
      (node (ref "Q29") (pin "1") (pinfunction "G_1") (pintype "passive"))
      (node (ref "R33") (pin "1") (pinfunction "1_1") (pintype "passive"))
      (node (ref "R34") (pin "1") (pinfunction "1_1") (pintype "passive"))
    )
    (net (code "48") (name "Net-(Q27-S)") (class "Default")
      (node (ref "Q27") (pin "2") (pinfunction "S_2") (pintype "passive"))
      (node (ref "Q28") (pin "3") (pinfunction "D_3") (pintype "passive"))
    )
    (net (code "49") (name "Net-(Q29-D)") (class "Default")
      (node (ref "Q29") (pin "3") (pinfunction "D_3") (pintype "passive"))
      (node (ref "R32") (pin "1") (pinfunction "1_1") (pintype "passive"))
      (node (ref "T5") (pin "1") (pinfunction "B_1") (pintype "passive"))
    )
    (net (code "50") (name "Net-(Q30-B)") (class "Default")
      (node (ref "Q30") (pin "1") (pinfunction "B_1") (pintype "passive"))
      (node (ref "R40") (pin "2") (pinfunction "2_2") (pintype "passive"))
    )
    (net (code "51") (name "Net-(Q30-C)") (class "Default")
      (node (ref "D6") (pin "A") (pinfunction "A_A") (pintype "passive"))
      (node (ref "Q30") (pin "3") (pinfunction "C_3") (pintype "passive"))
    )
    (net (code "52") (name "Net-(Q30-E)") (class "Default")
      (node (ref "Q30") (pin "2") (pinfunction "E_2") (pintype "passive"))
      (node (ref "R38") (pin "1") (pinfunction "1_1") (pintype "passive"))
      (node (ref "T6") (pin "3") (pinfunction "C_3") (pintype "passive"))
    )
    (net (code "53") (name "Net-(Q31-D)") (class "Default")
      (node (ref "Q31") (pin "3") (pinfunction "D_3") (pintype "passive"))
      (node (ref "Q33") (pin "1") (pinfunction "G_1") (pintype "passive"))
      (node (ref "R40") (pin "1") (pinfunction "1_1") (pintype "passive"))
      (node (ref "R41") (pin "1") (pinfunction "1_1") (pintype "passive"))
    )
    (net (code "54") (name "Net-(Q31-S)") (class "Default")
      (node (ref "Q31") (pin "2") (pinfunction "S_2") (pintype "passive"))
      (node (ref "Q32") (pin "3") (pinfunction "D_3") (pintype "passive"))
    )
    (net (code "55") (name "Net-(Q33-D)") (class "Default")
      (node (ref "Q33") (pin "3") (pinfunction "D_3") (pintype "passive"))
      (node (ref "R39") (pin "1") (pinfunction "1_1") (pintype "passive"))
      (node (ref "T6") (pin "1") (pinfunction "B_1") (pintype "passive"))
    )
    (net (code "56") (name "Net-(Q34-B)") (class "Default")
      (node (ref "Q34") (pin "1") (pinfunction "B_1") (pintype "passive"))
      (node (ref "R47") (pin "2") (pinfunction "2_2") (pintype "passive"))
    )
    (net (code "57") (name "Net-(Q34-C)") (class "Default")
      (node (ref "D7") (pin "A") (pinfunction "A_A") (pintype "passive"))
      (node (ref "Q34") (pin "3") (pinfunction "C_3") (pintype "passive"))
    )
    (net (code "58") (name "Net-(Q34-E)") (class "Default")
      (node (ref "Q34") (pin "2") (pinfunction "E_2") (pintype "passive"))
      (node (ref "R45") (pin "1") (pinfunction "1_1") (pintype "passive"))
      (node (ref "T7") (pin "3") (pinfunction "C_3") (pintype "passive"))
    )
    (net (code "59") (name "Net-(Q35-D)") (class "Default")
      (node (ref "Q35") (pin "3") (pinfunction "D_3") (pintype "passive"))
      (node (ref "Q37") (pin "1") (pinfunction "G_1") (pintype "passive"))
      (node (ref "R47") (pin "1") (pinfunction "1_1") (pintype "passive"))
      (node (ref "R48") (pin "1") (pinfunction "1_1") (pintype "passive"))
    )
    (net (code "60") (name "Net-(Q35-S)") (class "Default")
      (node (ref "Q35") (pin "2") (pinfunction "S_2") (pintype "passive"))
      (node (ref "Q36") (pin "3") (pinfunction "D_3") (pintype "passive"))
    )
    (net (code "61") (name "Net-(Q37-D)") (class "Default")
      (node (ref "Q37") (pin "3") (pinfunction "D_3") (pintype "passive"))
      (node (ref "R46") (pin "1") (pinfunction "1_1") (pintype "passive"))
      (node (ref "T7") (pin "1") (pinfunction "B_1") (pintype "passive"))
    )
    (net (code "62") (name "Net-(Q38-B)") (class "Default")
      (node (ref "Q38") (pin "1") (pinfunction "B_1") (pintype "passive"))
      (node (ref "R3") (pin "2") (pinfunction "2_2") (pintype "passive"))
    )
    (net (code "63") (name "Net-(Q38-C)") (class "Default")
      (node (ref "D8") (pin "A") (pinfunction "A_A") (pintype "passive"))
      (node (ref "Q38") (pin "3") (pinfunction "C_3") (pintype "passive"))
    )
    (net (code "64") (name "Net-(Q38-E)") (class "Default")
      (node (ref "Q38") (pin "2") (pinfunction "E_2") (pintype "passive"))
      (node (ref "R1") (pin "1") (pinfunction "1_1") (pintype "passive"))
      (node (ref "T8") (pin "3") (pinfunction "C_3") (pintype "passive"))
    )
    (net (code "65") (name "Net-(Q39-D)") (class "Default")
      (node (ref "Q39") (pin "3") (pinfunction "D_3") (pintype "passive"))
      (node (ref "Q41") (pin "1") (pinfunction "G_1") (pintype "passive"))
      (node (ref "R3") (pin "1") (pinfunction "1_1") (pintype "passive"))
      (node (ref "R4") (pin "1") (pinfunction "1_1") (pintype "passive"))
    )
    (net (code "66") (name "Net-(Q39-S)") (class "Default")
      (node (ref "Q39") (pin "2") (pinfunction "S_2") (pintype "passive"))
      (node (ref "Q40") (pin "3") (pinfunction "D_3") (pintype "passive"))
    )
    (net (code "67") (name "Net-(Q41-D)") (class "Default")
      (node (ref "Q41") (pin "3") (pinfunction "D_3") (pintype "passive"))
      (node (ref "R2") (pin "1") (pinfunction "1_1") (pintype "passive"))
      (node (ref "T8") (pin "1") (pinfunction "B_1") (pintype "passive"))
    )
    (net (code "68") (name "Net-(T1-B)") (class "Default")
      (node (ref "R10") (pin "1") (pinfunction "1_1") (pintype "passive"))
      (node (ref "R9") (pin "2") (pinfunction "2_2") (pintype "passive"))
      (node (ref "T1") (pin "1") (pinfunction "B_1") (pintype "passive"))
    )
    (net (code "69") (name "Net-(T1-E)") (class "Default")
      (node (ref "T1") (pin "2") (pinfunction "E_2") (pintype "passive"))
      (node (ref "T2") (pin "2") (pinfunction "E_2") (pintype "passive"))
      (node (ref "T3") (pin "3") (pinfunction "C_3") (pintype "passive"))
    )
    (net (code "70") (name "Net-(T3-B)") (class "Default")
      (node (ref "D2") (pin "A") (pinfunction "A_A") (pintype "passive"))
      (node (ref "R16") (pin "2") (pinfunction "2_2") (pintype "passive"))
      (node (ref "T3") (pin "1") (pinfunction "B_1") (pintype "passive"))
    )
    (net (code "71") (name "Net-(T3-E)") (class "Default")
      (node (ref "R17") (pin "1") (pinfunction "1_1") (pintype "passive"))
      (node (ref "T3") (pin "2") (pinfunction "E_2") (pintype "passive"))
    )
    (net (code "72") (name "unconnected-(SV1-Pad9)") (class "Default")
      (node (ref "SV1") (pin "9") (pinfunction "9_9") (pintype "passive"))
    )
    (net (code "73") (name "unconnected-(SV1-Pad10)") (class "Default")
      (node (ref "SV1") (pin "10") (pinfunction "10_10") (pintype "passive"))
    )
  )
)
